# team6.net
KiCad netlist of a schematic drawn in EAGLE
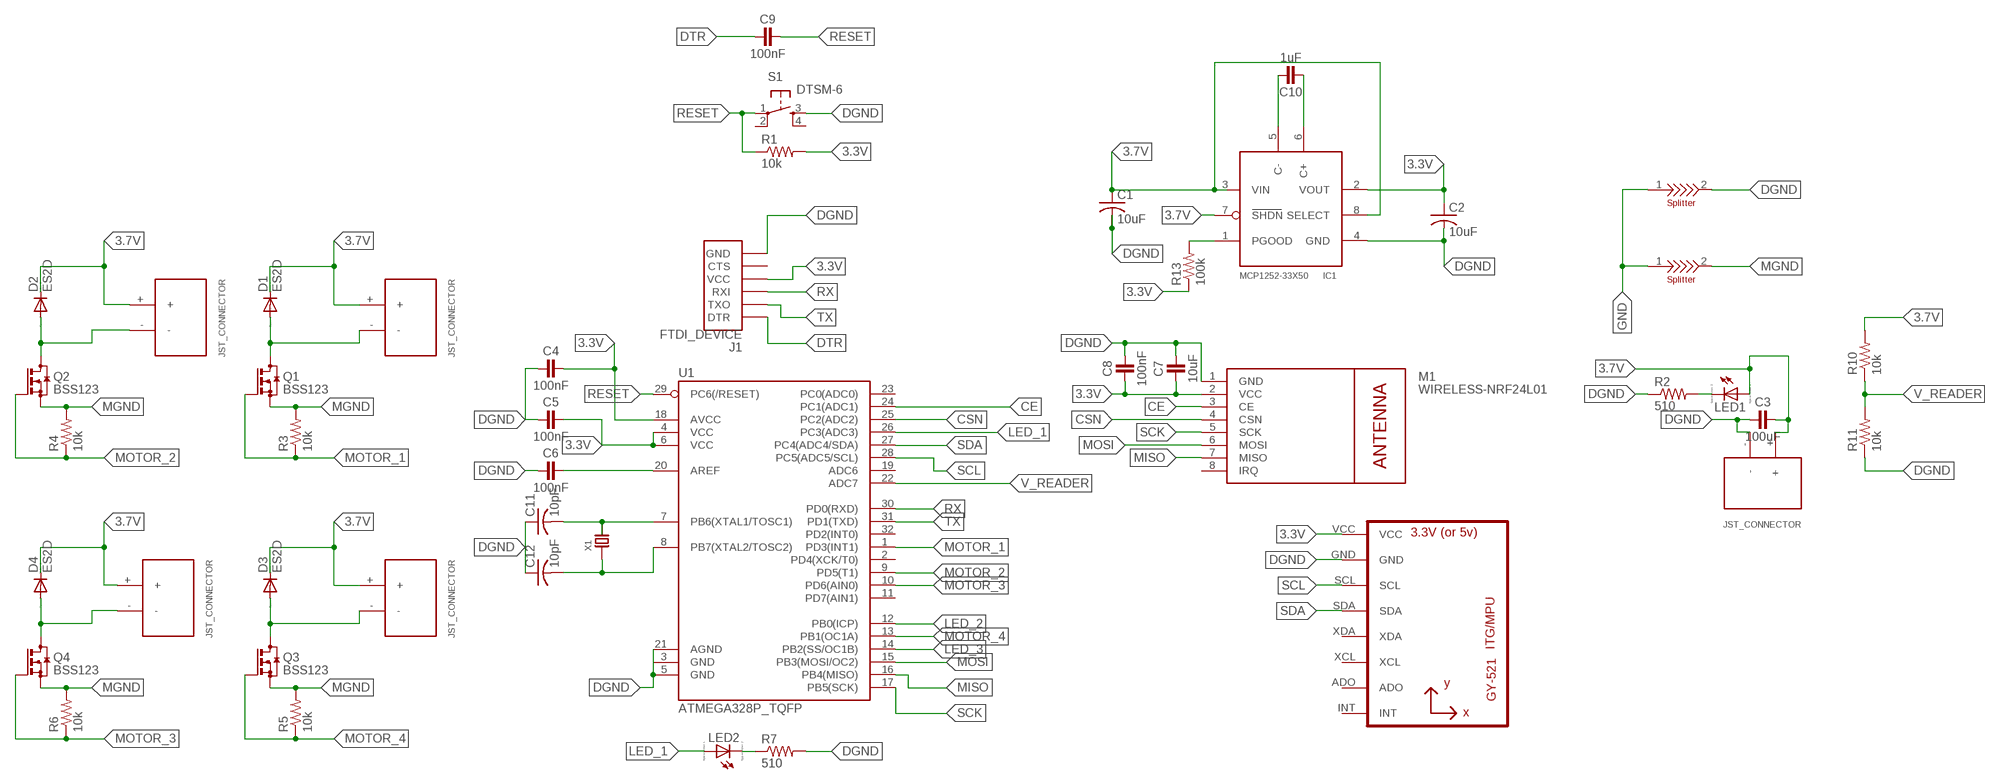
[diagram p0: schematic, sheet 1]

(export (version "E")
  (design (tool "Eeschema 10.0.6"))
  (components
    (comp (ref "C1")
      (value "10uF")
      (footprint "eagle-import:C1206")
      (libsource (lib "eagle-import") (part "C-USC1206"))
    )
    (comp (ref "C2")
      (value "10uF")
      (footprint "eagle-import:C1206")
      (libsource (lib "eagle-import") (part "C-USC1206"))
    )
    (comp (ref "C3")
      (value "100uF")
      (footprint "eagle-import:C1206")
      (libsource (lib "eagle-import") (part "CAPACITOR-1206"))
    )
    (comp (ref "C4")
      (value "100nF")
      (footprint "eagle-import:C0603")
      (libsource (lib "eagle-import") (part "CAPACITOR-0603"))
    )
    (comp (ref "C5")
      (value "100nF")
      (footprint "eagle-import:C0603")
      (libsource (lib "eagle-import") (part "CAPACITOR-0603"))
    )
    (comp (ref "C6")
      (value "100nF")
      (footprint "eagle-import:C0603")
      (libsource (lib "eagle-import") (part "CAPACITOR-0603"))
    )
    (comp (ref "C7")
      (value "10uF")
      (footprint "eagle-import:C0603")
      (libsource (lib "eagle-import") (part "CAPACITOR-0603"))
    )
    (comp (ref "C8")
      (value "100nF")
      (footprint "eagle-import:C0603")
      (libsource (lib "eagle-import") (part "CAPACITOR-0603"))
    )
    (comp (ref "C9")
      (value "100nF")
      (footprint "eagle-import:C0603")
      (libsource (lib "eagle-import") (part "CAPACITOR-0603"))
    )
    (comp (ref "C10")
      (value "1uF")
      (footprint "eagle-import:C0603")
      (libsource (lib "eagle-import") (part "CAPACITOR-0603"))
    )
    (comp (ref "C11")
      (value "10pF")
      (footprint "eagle-import:RCL_C0603K")
      (libsource (lib "eagle-import") (part "RCL_C-USC0603K"))
    )
    (comp (ref "C12")
      (value "10pF")
      (footprint "eagle-import:RCL_C0603K")
      (libsource (lib "eagle-import") (part "RCL_C-USC0603K"))
    )
    (comp (ref "D1")
      (value "ES2D")
      (footprint "eagle-import:SMB")
      (libsource (lib "eagle-import") (part "ES2D"))
    )
    (comp (ref "D2")
      (value "ES2D")
      (footprint "eagle-import:SMB")
      (libsource (lib "eagle-import") (part "ES2D"))
    )
    (comp (ref "D3")
      (value "ES2D")
      (footprint "eagle-import:SMB")
      (libsource (lib "eagle-import") (part "ES2D"))
    )
    (comp (ref "D4")
      (value "ES2D")
      (footprint "eagle-import:SMB")
      (libsource (lib "eagle-import") (part "ES2D"))
    )
    (comp (ref "IC1")
      (value "MCP1252-33X50")
      (footprint "eagle-import:MSOP8")
      (libsource (lib "eagle-import") (part "MCP1252-33X50"))
    )
    (comp (ref "J1")
      (value "FTDI_DEVICE")
      (footprint "eagle-import:FTDI_DEVICE_SIDE")
      (libsource (lib "eagle-import") (part "FTDI_DEVICE"))
    )
    (comp (ref "JST_MOTOR_1")
      (value "JST_MOTOR_1")
      (footprint "eagle-import:JST_CONNECTOR_FEMALE")
      (libsource (lib "eagle-import") (part "JST_CONNECTOR_FEMALE"))
    )
    (comp (ref "LED1")
      (value "LED_ESML0603")
      (footprint "eagle-import:LED_SML0603")
      (libsource (lib "eagle-import") (part "LED_ESML0603"))
    )
    (comp (ref "LED2")
      (value "LED_ESML0603")
      (footprint "eagle-import:LED_SML0603")
      (libsource (lib "eagle-import") (part "LED_ESML0603"))
    )
    (comp (ref "M1")
      (value "WIRELESS-NRF24L01")
      (footprint "eagle-import:WIRELESS-NRF24L01")
      (libsource (lib "eagle-import") (part "WIRELESS-NRF24L01"))
    )
    (comp (ref "Q1")
      (value "BSS123")
      (footprint "eagle-import:SOT23")
      (libsource (lib "eagle-import") (part "BSS123"))
    )
    (comp (ref "Q2")
      (value "BSS123")
      (footprint "eagle-import:SOT23")
      (libsource (lib "eagle-import") (part "BSS123"))
    )
    (comp (ref "Q3")
      (value "BSS123")
      (footprint "eagle-import:SOT23")
      (libsource (lib "eagle-import") (part "BSS123"))
    )
    (comp (ref "Q4")
      (value "BSS123")
      (footprint "eagle-import:SOT23")
      (libsource (lib "eagle-import") (part "BSS123"))
    )
    (comp (ref "R1")
      (value "10k")
      (footprint "eagle-import:0603")
      (libsource (lib "eagle-import") (part "10.5KOHM1/10W1%(0603)"))
    )
    (comp (ref "R2")
      (value "510")
      (footprint "eagle-import:0603")
      (libsource (lib "eagle-import") (part "10.5KOHM1/10W1%(0603)"))
    )
    (comp (ref "R3")
      (value "10k")
      (footprint "eagle-import:0603")
      (libsource (lib "eagle-import") (part "10.5KOHM1/10W1%(0603)"))
    )
    (comp (ref "R4")
      (value "10k")
      (footprint "eagle-import:0603")
      (libsource (lib "eagle-import") (part "10.5KOHM1/10W1%(0603)"))
    )
    (comp (ref "R5")
      (value "10k")
      (footprint "eagle-import:0603")
      (libsource (lib "eagle-import") (part "10.5KOHM1/10W1%(0603)"))
    )
    (comp (ref "R6")
      (value "10k")
      (footprint "eagle-import:0603")
      (libsource (lib "eagle-import") (part "10.5KOHM1/10W1%(0603)"))
    )
    (comp (ref "R7")
      (value "510")
      (footprint "eagle-import:0603")
      (libsource (lib "eagle-import") (part "10.5KOHM1/10W1%(0603)"))
    )
    (comp (ref "R10")
      (value "10k")
      (footprint "eagle-import:0603")
      (libsource (lib "eagle-import") (part "10.5KOHM1/10W1%(0603)"))
    )
    (comp (ref "R11")
      (value "10k")
      (footprint "eagle-import:0603")
      (libsource (lib "eagle-import") (part "10.5KOHM1/10W1%(0603)"))
    )
    (comp (ref "R13")
      (value "100k")
      (footprint "eagle-import:0603")
      (libsource (lib "eagle-import") (part "10.5KOHM1/10W1%(0603)"))
    )
    (comp (ref "S1")
      (value "DTSM-6")
      (footprint "eagle-import:DTSM-6")
      (libsource (lib "eagle-import") (part "DTSM-6"))
    )
    (comp (ref "U$2")
      (value "JST_CONNECTOR_FEMALE")
      (footprint "eagle-import:JST_CONNECTOR_FEMALE")
      (libsource (lib "eagle-import") (part "JST_CONNECTOR_FEMALE"))
    )
    (comp (ref "U$3")
      (value "JST_CONNECTOR_FEMALE")
      (footprint "eagle-import:JST_CONNECTOR_FEMALE")
      (libsource (lib "eagle-import") (part "JST_CONNECTOR_FEMALE"))
    )
    (comp (ref "U$4")
      (value "JST_CONNECTOR_FEMALE")
      (footprint "eagle-import:JST_CONNECTOR_FEMALE")
      (libsource (lib "eagle-import") (part "JST_CONNECTOR_FEMALE"))
    )
    (comp (ref "U$5")
      (value "JST_CONNECTOR_FEMALE")
      (footprint "eagle-import:JST_CONNECTOR_FEMALE")
      (libsource (lib "eagle-import") (part "JST_CONNECTOR_FEMALE"))
    )
    (comp (ref "U$7")
      (value "SPLITTER")
      (footprint "eagle-import:SPLITTER")
      (libsource (lib "eagle-import") (part "SPLITTER"))
    )
    (comp (ref "U$8")
      (value "SPLITTER")
      (footprint "eagle-import:SPLITTER")
      (libsource (lib "eagle-import") (part "SPLITTER"))
    )
    (comp (ref "U1")
      (value "ATMEGA328P_TQFP")
      (footprint "eagle-import:TQFP32-08")
      (libsource (lib "eagle-import") (part "ATMEGA328P_TQFP"))
    )
    (comp (ref "U3")
      (value "GY-521MPU6050")
      (footprint "eagle-import:GY-521")
      (libsource (lib "eagle-import") (part "GY-521MPU6050"))
    )
    (comp (ref "X1")
      (value "CRYSTAL-NX3225GD")
      (footprint "eagle-import:NDK-NX3225GD")
      (libsource (lib "eagle-import") (part "CRYSTAL-NX3225GD"))
    )
  )
  (nets
    (net (code "1") (name "3.3V") (class "Default")
      (node (ref "C2") (pin "1") (pinfunction "1_1") (pintype "passive"))
      (node (ref "C4") (pin "2") (pinfunction "2_2") (pintype "passive"))
      (node (ref "C5") (pin "2") (pinfunction "2_2") (pintype "passive"))
      (node (ref "C7") (pin "1") (pinfunction "1_1") (pintype "passive"))
      (node (ref "C8") (pin "1") (pinfunction "1_1") (pintype "passive"))
      (node (ref "IC1") (pin "2") (pinfunction "VOUT_2") (pintype "output"))
      (node (ref "J1") (pin "P$4") (pinfunction "VCC_P$4") (pintype "bidirectional"))
      (node (ref "M1") (pin "2") (pinfunction "VCC_2") (pintype "power_in"))
      (node (ref "R1") (pin "2") (pinfunction "2_2") (pintype "passive"))
      (node (ref "R13") (pin "1") (pinfunction "1_1") (pintype "passive"))
      (node (ref "U1") (pin "18") (pinfunction "AVCC_18") (pintype "bidirectional"))
      (node (ref "U1") (pin "4") (pinfunction "VCC_4") (pintype "bidirectional"))
      (node (ref "U1") (pin "6") (pinfunction "VCC_6") (pintype "bidirectional"))
      (node (ref "U3") (pin "VCC") (pinfunction "VCC_VCC") (pintype "bidirectional"))
    )
    (net (code "2") (name "3.7V") (class "Default")
      (node (ref "C1") (pin "1") (pinfunction "1_1") (pintype "passive"))
      (node (ref "C3") (pin "2") (pinfunction "2_2") (pintype "passive"))
      (node (ref "D1") (pin "C") (pinfunction "C_C") (pintype "passive"))
      (node (ref "D2") (pin "C") (pinfunction "C_C") (pintype "passive"))
      (node (ref "D3") (pin "C") (pinfunction "C_C") (pintype "passive"))
      (node (ref "D4") (pin "C") (pinfunction "C_C") (pintype "passive"))
      (node (ref "IC1") (pin "3") (pinfunction "VIN_3") (pintype "power_in"))
      (node (ref "IC1") (pin "7") (pinfunction "SHDN_7") (pintype "input"))
      (node (ref "IC1") (pin "8") (pinfunction "SELECT_8") (pintype "input"))
      (node (ref "JST_MOTOR_1") (pin "+") (pinfunction "+_+") (pintype "bidirectional"))
      (node (ref "LED1") (pin "A") (pinfunction "A_A") (pintype "passive"))
      (node (ref "R10") (pin "2") (pinfunction "2_2") (pintype "passive"))
      (node (ref "U$2") (pin "+") (pinfunction "+_+") (pintype "bidirectional"))
      (node (ref "U$3") (pin "+") (pinfunction "+_+") (pintype "bidirectional"))
      (node (ref "U$4") (pin "+") (pinfunction "+_+") (pintype "bidirectional"))
      (node (ref "U$5") (pin "+") (pinfunction "+_+") (pintype "bidirectional"))
    )
    (net (code "3") (name "CE") (class "Default")
      (node (ref "M1") (pin "3") (pinfunction "CE_3") (pintype "bidirectional"))
      (node (ref "U1") (pin "24") (pinfunction "PC1(ADC1)_24") (pintype "bidirectional"))
    )
    (net (code "4") (name "CSN") (class "Default")
      (node (ref "M1") (pin "4") (pinfunction "CSN_4") (pintype "bidirectional"))
      (node (ref "U1") (pin "25") (pinfunction "PC2(ADC2)_25") (pintype "bidirectional"))
    )
    (net (code "5") (name "DGND") (class "Default")
      (node (ref "C1") (pin "2") (pinfunction "2_2") (pintype "passive"))
      (node (ref "C11") (pin "1") (pinfunction "1_1") (pintype "passive"))
      (node (ref "C12") (pin "1") (pinfunction "1_1") (pintype "passive"))
      (node (ref "C2") (pin "2") (pinfunction "2_2") (pintype "passive"))
      (node (ref "C3") (pin "1") (pinfunction "1_1") (pintype "passive"))
      (node (ref "C4") (pin "1") (pinfunction "1_1") (pintype "passive"))
      (node (ref "C5") (pin "1") (pinfunction "1_1") (pintype "passive"))
      (node (ref "C6") (pin "1") (pinfunction "1_1") (pintype "passive"))
      (node (ref "C7") (pin "2") (pinfunction "2_2") (pintype "passive"))
      (node (ref "C8") (pin "2") (pinfunction "2_2") (pintype "passive"))
      (node (ref "IC1") (pin "4") (pinfunction "GND_4") (pintype "power_in"))
      (node (ref "J1") (pin "P$6") (pinfunction "GND_P$6") (pintype "bidirectional"))
      (node (ref "M1") (pin "1") (pinfunction "GND_1") (pintype "power_in"))
      (node (ref "R11") (pin "1") (pinfunction "1_1") (pintype "passive"))
      (node (ref "R2") (pin "1") (pinfunction "1_1") (pintype "passive"))
      (node (ref "R7") (pin "2") (pinfunction "2_2") (pintype "passive"))
      (node (ref "S1") (pin "3") (pinfunction "3_3") (pintype "passive"))
      (node (ref "U$2") (pin "-") (pinfunction "-_-") (pintype "bidirectional"))
      (node (ref "U$8") (pin "2") (pinfunction "2_2") (pintype "bidirectional"))
      (node (ref "U1") (pin "21") (pinfunction "AGND_21") (pintype "bidirectional"))
      (node (ref "U1") (pin "3") (pinfunction "GND_3") (pintype "bidirectional"))
      (node (ref "U1") (pin "5") (pinfunction "GND_5") (pintype "bidirectional"))
      (node (ref "U3") (pin "GND") (pinfunction "GND_GND") (pintype "bidirectional"))
    )
    (net (code "6") (name "DTR") (class "Default")
      (node (ref "C9") (pin "1") (pinfunction "1_1") (pintype "passive"))
      (node (ref "J1") (pin "P$1") (pinfunction "DTR_P$1") (pintype "bidirectional"))
    )
    (net (code "7") (name "GND") (class "Default")
      (node (ref "U$7") (pin "1") (pinfunction "1_1") (pintype "bidirectional"))
      (node (ref "U$8") (pin "1") (pinfunction "1_1") (pintype "bidirectional"))
    )
    (net (code "8") (name "LED_1") (class "Default")
      (node (ref "LED2") (pin "A") (pinfunction "A_A") (pintype "passive"))
      (node (ref "U1") (pin "26") (pinfunction "PC3(ADC3)_26") (pintype "bidirectional"))
    )
    (net (code "9") (name "LED_2") (class "Default")
      (node (ref "U1") (pin "12") (pinfunction "PB0(ICP)_12") (pintype "bidirectional"))
    )
    (net (code "10") (name "LED_3") (class "Default")
      (node (ref "U1") (pin "14") (pinfunction "PB2(SS/OC1B)_14") (pintype "bidirectional"))
    )
    (net (code "11") (name "MGND") (class "Default")
      (node (ref "Q1") (pin "2") (pinfunction "S_2") (pintype "passive"))
      (node (ref "Q2") (pin "2") (pinfunction "S_2") (pintype "passive"))
      (node (ref "Q3") (pin "2") (pinfunction "S_2") (pintype "passive"))
      (node (ref "Q4") (pin "2") (pinfunction "S_2") (pintype "passive"))
      (node (ref "R3") (pin "2") (pinfunction "2_2") (pintype "passive"))
      (node (ref "R4") (pin "2") (pinfunction "2_2") (pintype "passive"))
      (node (ref "R5") (pin "2") (pinfunction "2_2") (pintype "passive"))
      (node (ref "R6") (pin "2") (pinfunction "2_2") (pintype "passive"))
      (node (ref "U$7") (pin "2") (pinfunction "2_2") (pintype "bidirectional"))
    )
    (net (code "12") (name "MISO") (class "Default")
      (node (ref "M1") (pin "7") (pinfunction "MISO_7") (pintype "bidirectional"))
      (node (ref "U1") (pin "16") (pinfunction "PB4(MISO)_16") (pintype "bidirectional"))
    )
    (net (code "13") (name "MOSI") (class "Default")
      (node (ref "M1") (pin "6") (pinfunction "MOSI_6") (pintype "bidirectional"))
      (node (ref "U1") (pin "15") (pinfunction "PB3(MOSI/OC2)_15") (pintype "bidirectional"))
    )
    (net (code "14") (name "MOTOR_1") (class "Default")
      (node (ref "Q1") (pin "1") (pinfunction "G_1") (pintype "passive"))
      (node (ref "R3") (pin "1") (pinfunction "1_1") (pintype "passive"))
      (node (ref "U1") (pin "1") (pinfunction "PD3(INT1)_1") (pintype "bidirectional"))
    )
    (net (code "15") (name "MOTOR_2") (class "Default")
      (node (ref "Q2") (pin "1") (pinfunction "G_1") (pintype "passive"))
      (node (ref "R4") (pin "1") (pinfunction "1_1") (pintype "passive"))
      (node (ref "U1") (pin "9") (pinfunction "PD5(T1)_9") (pintype "bidirectional"))
    )
    (net (code "16") (name "MOTOR_3") (class "Default")
      (node (ref "Q4") (pin "1") (pinfunction "G_1") (pintype "passive"))
      (node (ref "R6") (pin "1") (pinfunction "1_1") (pintype "passive"))
      (node (ref "U1") (pin "10") (pinfunction "PD6(AIN0)_10") (pintype "bidirectional"))
    )
    (net (code "17") (name "MOTOR_4") (class "Default")
      (node (ref "Q3") (pin "1") (pinfunction "G_1") (pintype "passive"))
      (node (ref "R5") (pin "1") (pinfunction "1_1") (pintype "passive"))
      (node (ref "U1") (pin "13") (pinfunction "PB1(OC1A)_13") (pintype "bidirectional"))
    )
    (net (code "18") (name "Net-(IC1-C+)") (class "Default")
      (node (ref "C10") (pin "1") (pinfunction "1_1") (pintype "passive"))
      (node (ref "IC1") (pin "6") (pinfunction "C+_6") (pintype "passive"))
    )
    (net (code "19") (name "Net-(IC1-C-)") (class "Default")
      (node (ref "C10") (pin "2") (pinfunction "2_2") (pintype "passive"))
      (node (ref "IC1") (pin "5") (pinfunction "C-_5") (pintype "passive"))
    )
    (net (code "20") (name "Net-(IC1-PGOOD)") (class "Default")
      (node (ref "IC1") (pin "1") (pinfunction "PGOOD_1") (pintype "output"))
      (node (ref "R13") (pin "2") (pinfunction "2_2") (pintype "passive"))
    )
    (net (code "21") (name "Net-(LED1-PadC)") (class "Default")
      (node (ref "LED1") (pin "C") (pinfunction "C_C") (pintype "passive"))
      (node (ref "R2") (pin "2") (pinfunction "2_2") (pintype "passive"))
    )
    (net (code "22") (name "Net-(LED2-PadC)") (class "Default")
      (node (ref "LED2") (pin "C") (pinfunction "C_C") (pintype "passive"))
      (node (ref "R7") (pin "1") (pinfunction "1_1") (pintype "passive"))
    )
    (net (code "23") (name "Net-(Q1-D)") (class "Default")
      (node (ref "D1") (pin "A") (pinfunction "A_A") (pintype "passive"))
      (node (ref "JST_MOTOR_1") (pin "-") (pinfunction "-_-") (pintype "bidirectional"))
      (node (ref "Q1") (pin "3") (pinfunction "D_3") (pintype "passive"))
    )
    (net (code "24") (name "Net-(Q2-D)") (class "Default")
      (node (ref "D2") (pin "A") (pinfunction "A_A") (pintype "passive"))
      (node (ref "Q2") (pin "3") (pinfunction "D_3") (pintype "passive"))
      (node (ref "U$3") (pin "-") (pinfunction "-_-") (pintype "bidirectional"))
    )
    (net (code "25") (name "Net-(Q3-D)") (class "Default")
      (node (ref "D3") (pin "A") (pinfunction "A_A") (pintype "passive"))
      (node (ref "Q3") (pin "3") (pinfunction "D_3") (pintype "passive"))
      (node (ref "U$5") (pin "-") (pinfunction "-_-") (pintype "bidirectional"))
    )
    (net (code "26") (name "Net-(Q4-D)") (class "Default")
      (node (ref "D4") (pin "A") (pinfunction "A_A") (pintype "passive"))
      (node (ref "Q4") (pin "3") (pinfunction "D_3") (pintype "passive"))
      (node (ref "U$4") (pin "-") (pinfunction "-_-") (pintype "bidirectional"))
    )
    (net (code "27") (name "Net-(U1-AREF)") (class "Default")
      (node (ref "C6") (pin "2") (pinfunction "2_2") (pintype "passive"))
      (node (ref "U1") (pin "20") (pinfunction "AREF_20") (pintype "bidirectional"))
    )
    (net (code "28") (name "Net-(U1-PB6(XTAL1{slash}TOSC1))") (class "Default")
      (node (ref "C11") (pin "2") (pinfunction "2_2") (pintype "passive"))
      (node (ref "U1") (pin "7") (pinfunction "PB6(XTAL1/TOSC1)_7") (pintype "bidirectional"))
      (node (ref "X1") (pin "2") (pinfunction "P$2_2") (pintype "bidirectional"))
    )
    (net (code "29") (name "Net-(U1-PB7(XTAL2{slash}TOSC2))") (class "Default")
      (node (ref "C12") (pin "2") (pinfunction "2_2") (pintype "passive"))
      (node (ref "U1") (pin "8") (pinfunction "PB7(XTAL2/TOSC2)_8") (pintype "bidirectional"))
      (node (ref "X1") (pin "1") (pinfunction "P$1_1") (pintype "bidirectional"))
    )
    (net (code "30") (name "RESET") (class "Default")
      (node (ref "C9") (pin "2") (pinfunction "2_2") (pintype "passive"))
      (node (ref "R1") (pin "1") (pinfunction "1_1") (pintype "passive"))
      (node (ref "S1") (pin "1") (pinfunction "1_1") (pintype "passive"))
      (node (ref "U1") (pin "29") (pinfunction "PC6(/RESET)_29") (pintype "bidirectional"))
    )
    (net (code "31") (name "RX") (class "Default")
      (node (ref "J1") (pin "P$3") (pinfunction "RXI_P$3") (pintype "bidirectional"))
      (node (ref "U1") (pin "30") (pinfunction "PD0(RXD)_30") (pintype "bidirectional"))
    )
    (net (code "32") (name "SCK") (class "Default")
      (node (ref "M1") (pin "5") (pinfunction "SCK_5") (pintype "bidirectional"))
      (node (ref "U1") (pin "17") (pinfunction "PB5(SCK)_17") (pintype "bidirectional"))
    )
    (net (code "33") (name "SCL") (class "Default")
      (node (ref "U1") (pin "28") (pinfunction "PC5(ADC5/SCL)_28") (pintype "bidirectional"))
      (node (ref "U3") (pin "SCL") (pinfunction "SCL_SCL") (pintype "bidirectional"))
    )
    (net (code "34") (name "SDA") (class "Default")
      (node (ref "U1") (pin "27") (pinfunction "PC4(ADC4/SDA)_27") (pintype "bidirectional"))
      (node (ref "U3") (pin "SDA") (pinfunction "SDA_SDA") (pintype "bidirectional"))
    )
    (net (code "35") (name "TX") (class "Default")
      (node (ref "J1") (pin "P$2") (pinfunction "TXO_P$2") (pintype "bidirectional"))
      (node (ref "U1") (pin "31") (pinfunction "PD1(TXD)_31") (pintype "bidirectional"))
    )
    (net (code "36") (name "V_READER") (class "Default")
      (node (ref "R10") (pin "1") (pinfunction "1_1") (pintype "passive"))
      (node (ref "R11") (pin "2") (pinfunction "2_2") (pintype "passive"))
      (node (ref "U1") (pin "22") (pinfunction "ADC7_22") (pintype "bidirectional"))
    )
    (net (code "37") (name "unconnected-(J1-CTS-PadP$5)") (class "Default")
      (node (ref "J1") (pin "P$5") (pinfunction "CTS_P$5") (pintype "bidirectional"))
    )
    (net (code "38") (name "unconnected-(M1-IRQ-Pad8)") (class "Default")
      (node (ref "M1") (pin "8") (pinfunction "IRQ_8") (pintype "bidirectional"))
    )
    (net (code "39") (name "unconnected-(S1-Pad2)") (class "Default")
      (node (ref "S1") (pin "2") (pinfunction "2_2") (pintype "passive"))
    )
    (net (code "40") (name "unconnected-(S1-Pad4)") (class "Default")
      (node (ref "S1") (pin "4") (pinfunction "4_4") (pintype "passive"))
    )
    (net (code "41") (name "unconnected-(U1-ADC6-Pad19)") (class "Default")
      (node (ref "U1") (pin "19") (pinfunction "ADC6_19") (pintype "bidirectional"))
    )
    (net (code "42") (name "unconnected-(U1-PC0(ADC0)-Pad23)") (class "Default")
      (node (ref "U1") (pin "23") (pinfunction "PC0(ADC0)_23") (pintype "bidirectional"))
    )
    (net (code "43") (name "unconnected-(U1-PD2(INT0)-Pad32)") (class "Default")
      (node (ref "U1") (pin "32") (pinfunction "PD2(INT0)_32") (pintype "bidirectional"))
    )
    (net (code "44") (name "unconnected-(U1-PD4(XCK{slash}T0)-Pad2)") (class "Default")
      (node (ref "U1") (pin "2") (pinfunction "PD4(XCK/T0)_2") (pintype "bidirectional"))
    )
    (net (code "45") (name "unconnected-(U1-PD7(AIN1)-Pad11)") (class "Default")
      (node (ref "U1") (pin "11") (pinfunction "PD7(AIN1)_11") (pintype "bidirectional"))
    )
    (net (code "46") (name "unconnected-(U3-PadADO)") (class "Default")
      (node (ref "U3") (pin "ADO") (pinfunction "ADO_ADO") (pintype "bidirectional"))
    )
    (net (code "47") (name "unconnected-(U3-PadINT)") (class "Default")
      (node (ref "U3") (pin "INT") (pinfunction "INT_INT") (pintype "bidirectional"))
    )
    (net (code "48") (name "unconnected-(U3-PadXCL)") (class "Default")
      (node (ref "U3") (pin "XCL") (pinfunction "XCL_XCL") (pintype "bidirectional"))
    )
    (net (code "49") (name "unconnected-(U3-PadXDA)") (class "Default")
      (node (ref "U3") (pin "XDA") (pinfunction "XDA_XDA") (pintype "bidirectional"))
    )
  )
)
